# ts5_redraw.net
KiCad netlist of a schematic drawn in EAGLE
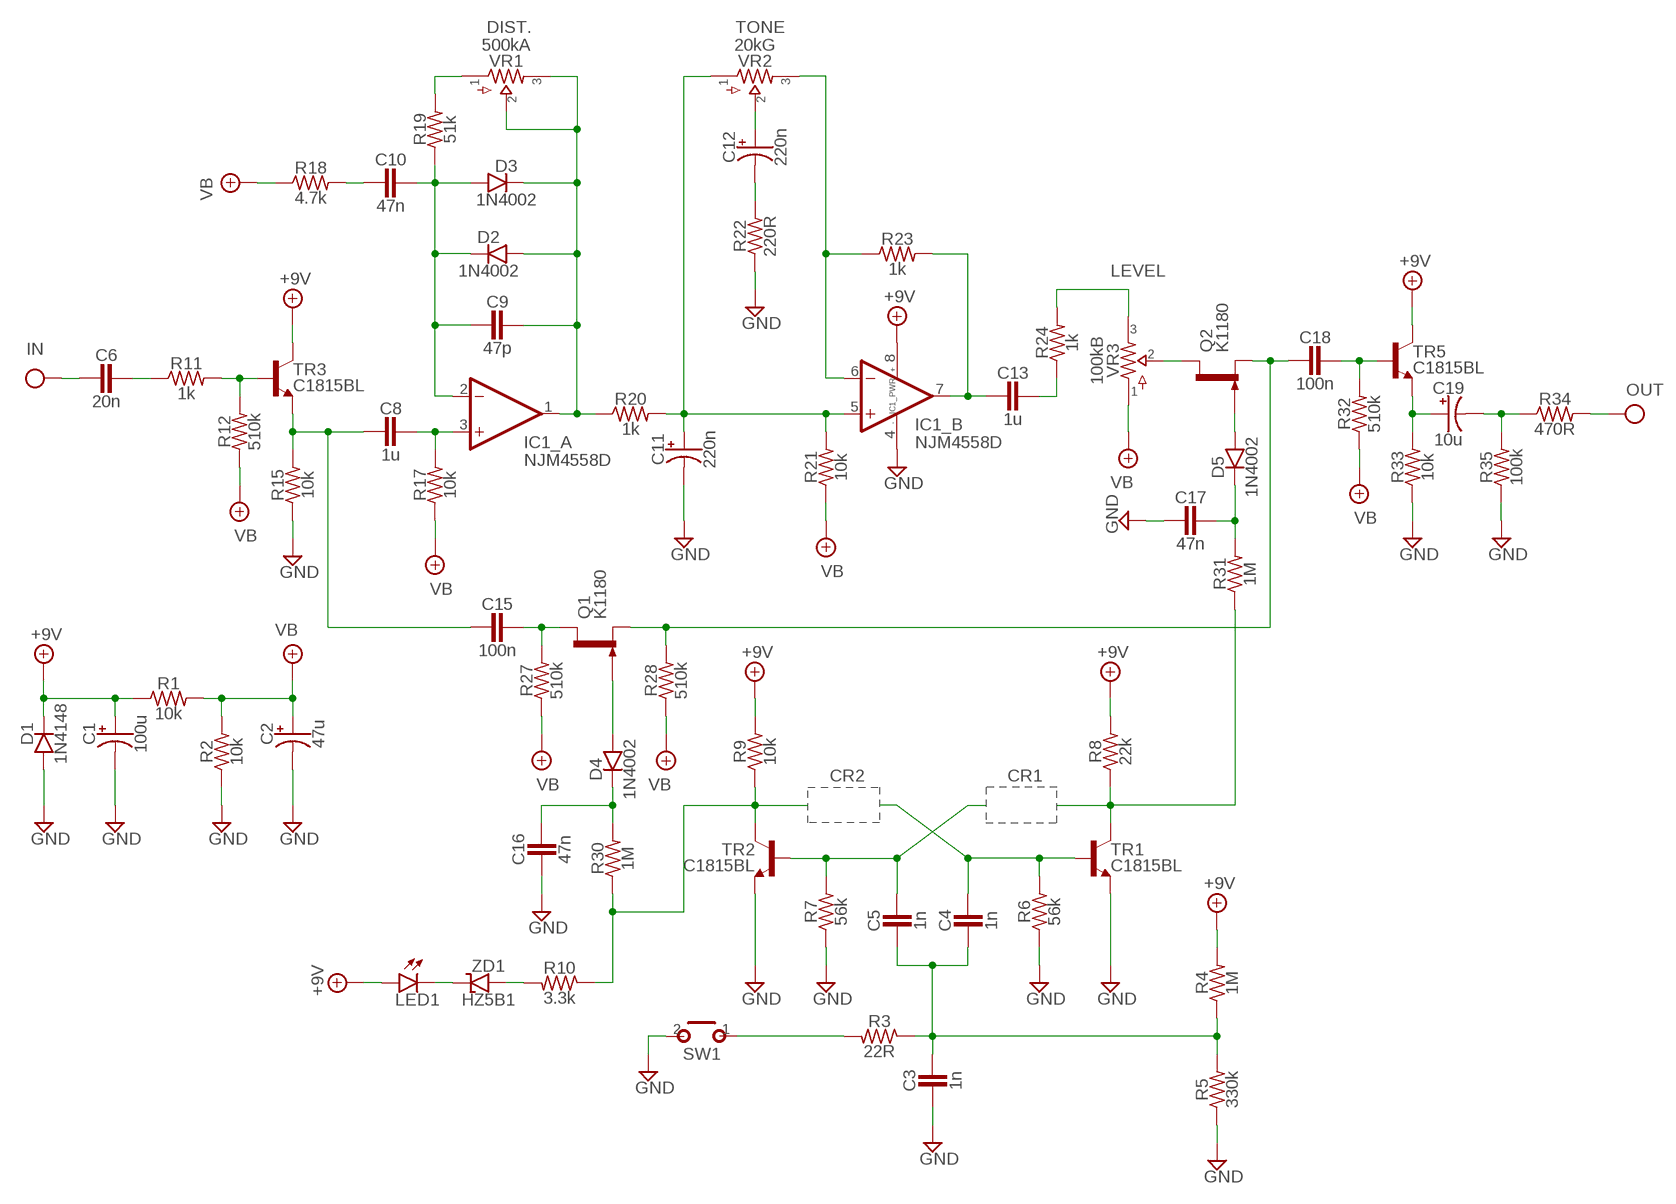
[diagram p0: schematic, sheet 1]

(export (version "E")
  (design (tool "Eeschema 10.0.6"))
  (components
    (comp (ref "C1")
      (value "100u")
      (footprint "eagle-import:050_020")
      (libsource (lib "eagle-import") (part "0500"))
    )
    (comp (ref "C2")
      (value "47u")
      (footprint "eagle-import:050_020")
      (libsource (lib "eagle-import") (part "0500"))
    )
    (comp (ref "C3")
      (value "1n")
      (footprint "eagle-import:BOX_SMALL")
      (libsource (lib "eagle-import") (part "CER/FILMBOX.1"))
    )
    (comp (ref "C4")
      (value "1n")
      (footprint "eagle-import:BOX_SMALL")
      (libsource (lib "eagle-import") (part "CER/FILMBOX.1"))
    )
    (comp (ref "C5")
      (value "1n")
      (footprint "eagle-import:BOX_SMALL")
      (libsource (lib "eagle-import") (part "CER/FILMBOX.1"))
    )
    (comp (ref "C6")
      (value "20n")
      (footprint "eagle-import:BOX_SMALL")
      (libsource (lib "eagle-import") (part "CER/FILMBOX.1"))
    )
    (comp (ref "C8")
      (value "1u")
      (footprint "eagle-import:BOX_SMALL")
      (libsource (lib "eagle-import") (part "CER/FILMBOX.1"))
    )
    (comp (ref "C9")
      (value "47p")
      (footprint "eagle-import:BOX_SMALL")
      (libsource (lib "eagle-import") (part "CER/FILMBOX.1"))
    )
    (comp (ref "C10")
      (value "47n")
      (footprint "eagle-import:BOX_SMALL")
      (libsource (lib "eagle-import") (part "CER/FILMBOX.1"))
    )
    (comp (ref "C11")
      (value "220n")
      (footprint "eagle-import:050_020")
      (libsource (lib "eagle-import") (part "0500"))
    )
    (comp (ref "C12")
      (value "220n")
      (footprint "eagle-import:050_020")
      (libsource (lib "eagle-import") (part "0500"))
    )
    (comp (ref "C13")
      (value "1u")
      (footprint "eagle-import:BOX_SMALL")
      (libsource (lib "eagle-import") (part "CER/FILMBOX.1"))
    )
    (comp (ref "C15")
      (value "100n")
      (footprint "eagle-import:BOX_SMALL")
      (libsource (lib "eagle-import") (part "CER/FILMBOX.1"))
    )
    (comp (ref "C16")
      (value "47n")
      (footprint "eagle-import:BOX_SMALL")
      (libsource (lib "eagle-import") (part "CER/FILMBOX.1"))
    )
    (comp (ref "C17")
      (value "47n")
      (footprint "eagle-import:BOX_SMALL")
      (libsource (lib "eagle-import") (part "CER/FILMBOX.1"))
    )
    (comp (ref "C18")
      (value "100n")
      (footprint "eagle-import:BOX_SMALL")
      (libsource (lib "eagle-import") (part "CER/FILMBOX.1"))
    )
    (comp (ref "C19")
      (value "10u")
      (footprint "eagle-import:050_020")
      (libsource (lib "eagle-import") (part "0500"))
    )
    (comp (ref "D1")
      (value "1N4148")
      (footprint "eagle-import:DO35-2")
      (libsource (lib "eagle-import") (part "DO35.2"))
    )
    (comp (ref "D2")
      (value "1N4002")
      (footprint "eagle-import:DO35-2")
      (libsource (lib "eagle-import") (part "DO35.2"))
    )
    (comp (ref "D3")
      (value "1N4002")
      (footprint "eagle-import:DO35-2")
      (libsource (lib "eagle-import") (part "DO35.2"))
    )
    (comp (ref "D4")
      (value "1N4002")
      (footprint "eagle-import:DO35-2")
      (libsource (lib "eagle-import") (part "DO35.2"))
    )
    (comp (ref "D5")
      (value "1N4002")
      (footprint "eagle-import:DO35-2")
      (libsource (lib "eagle-import") (part "DO35.2"))
    )
    (comp (ref "IC1")
      (value "NJM4558D")
      (footprint "eagle-import:DIL0")
      (libsource (lib "eagle-import") (part "DUALTH"))
    )
    (comp (ref "LED1")
      (value "TLR124")
      (footprint "eagle-import:3MM_D")
      (libsource (lib "eagle-import") (part "LED"))
    )
    (comp (ref "Q1")
      (value "K1180")
      (footprint "eagle-import:TO92-")
      (libsource (lib "eagle-import") (part "2N5457"))
    )
    (comp (ref "Q2")
      (value "K1180")
      (footprint "eagle-import:TO92-")
      (libsource (lib "eagle-import") (part "2N5457"))
    )
    (comp (ref "R1")
      (value "10k")
      (footprint "eagle-import:R0207_3")
      (libsource (lib "eagle-import") (part "R_.3B"))
    )
    (comp (ref "R2")
      (value "10k")
      (footprint "eagle-import:R0207_3")
      (libsource (lib "eagle-import") (part "R_.3B"))
    )
    (comp (ref "R3")
      (value "22R")
      (footprint "eagle-import:R0207_3")
      (libsource (lib "eagle-import") (part "R_.3B"))
    )
    (comp (ref "R4")
      (value "1M")
      (footprint "eagle-import:R0207_3")
      (libsource (lib "eagle-import") (part "R_.3B"))
    )
    (comp (ref "R5")
      (value "330k")
      (footprint "eagle-import:R0207_3")
      (libsource (lib "eagle-import") (part "R_.3B"))
    )
    (comp (ref "R6")
      (value "56k")
      (footprint "eagle-import:R0207_3")
      (libsource (lib "eagle-import") (part "R_.3B"))
    )
    (comp (ref "R7")
      (value "56k")
      (footprint "eagle-import:R0207_3")
      (libsource (lib "eagle-import") (part "R_.3B"))
    )
    (comp (ref "R8")
      (value "22k")
      (footprint "eagle-import:R0207_3")
      (libsource (lib "eagle-import") (part "R_.3B"))
    )
    (comp (ref "R9")
      (value "10k")
      (footprint "eagle-import:R0207_3")
      (libsource (lib "eagle-import") (part "R_.3B"))
    )
    (comp (ref "R10")
      (value "3.3k")
      (footprint "eagle-import:R0207_3")
      (libsource (lib "eagle-import") (part "R_.3B"))
    )
    (comp (ref "R11")
      (value "1k")
      (footprint "eagle-import:R0207_3")
      (libsource (lib "eagle-import") (part "R_.3B"))
    )
    (comp (ref "R12")
      (value "510k")
      (footprint "eagle-import:R0207_3")
      (libsource (lib "eagle-import") (part "R_.3B"))
    )
    (comp (ref "R15")
      (value "10k")
      (footprint "eagle-import:R0207_3")
      (libsource (lib "eagle-import") (part "R_.3B"))
    )
    (comp (ref "R17")
      (value "10k")
      (footprint "eagle-import:R0207_3")
      (libsource (lib "eagle-import") (part "R_.3B"))
    )
    (comp (ref "R18")
      (value "4.7k")
      (footprint "eagle-import:R0207_3")
      (libsource (lib "eagle-import") (part "R_.3B"))
    )
    (comp (ref "R19")
      (value "51k")
      (footprint "eagle-import:R0207_3")
      (libsource (lib "eagle-import") (part "R_.3B"))
    )
    (comp (ref "R20")
      (value "1k")
      (footprint "eagle-import:R0207_3")
      (libsource (lib "eagle-import") (part "R_.3B"))
    )
    (comp (ref "R21")
      (value "10k")
      (footprint "eagle-import:R0207_3")
      (libsource (lib "eagle-import") (part "R_.3B"))
    )
    (comp (ref "R22")
      (value "220R")
      (footprint "eagle-import:R0207_3")
      (libsource (lib "eagle-import") (part "R_.3B"))
    )
    (comp (ref "R23")
      (value "1k")
      (footprint "eagle-import:R0207_3")
      (libsource (lib "eagle-import") (part "R_.3B"))
    )
    (comp (ref "R24")
      (value "1k")
      (footprint "eagle-import:R0207_3")
      (libsource (lib "eagle-import") (part "R_.3B"))
    )
    (comp (ref "R27")
      (value "510k")
      (footprint "eagle-import:R0207_3")
      (libsource (lib "eagle-import") (part "R_.3B"))
    )
    (comp (ref "R28")
      (value "510k")
      (footprint "eagle-import:R0207_3")
      (libsource (lib "eagle-import") (part "R_.3B"))
    )
    (comp (ref "R30")
      (value "1M")
      (footprint "eagle-import:R0207_3")
      (libsource (lib "eagle-import") (part "R_.3B"))
    )
    (comp (ref "R31")
      (value "1M")
      (footprint "eagle-import:R0207_3")
      (libsource (lib "eagle-import") (part "R_.3B"))
    )
    (comp (ref "R32")
      (value "510k")
      (footprint "eagle-import:R0207_3")
      (libsource (lib "eagle-import") (part "R_.3B"))
    )
    (comp (ref "R33")
      (value "10k")
      (footprint "eagle-import:R0207_3")
      (libsource (lib "eagle-import") (part "R_.3B"))
    )
    (comp (ref "R34")
      (value "470R")
      (footprint "eagle-import:R0207_3")
      (libsource (lib "eagle-import") (part "R_.3B"))
    )
    (comp (ref "R35")
      (value "100k")
      (footprint "eagle-import:R0207_3")
      (libsource (lib "eagle-import") (part "R_.3B"))
    )
    (comp (ref "SW1")
      (value "MOMENTARY")
      (footprint "eagle-import:SPST")
      (libsource (lib "eagle-import") (part "MOMENTARY"))
    )
    (comp (ref "TR1")
      (value "C1815BL")
      (footprint "eagle-import:TO92-")
      (libsource (lib "eagle-import") (part "2SC828A"))
    )
    (comp (ref "TR2")
      (value "C1815BL")
      (footprint "eagle-import:TO92-")
      (libsource (lib "eagle-import") (part "2SC828A"))
    )
    (comp (ref "TR3")
      (value "C1815BL")
      (footprint "eagle-import:TO92-")
      (libsource (lib "eagle-import") (part "2N3904"))
    )
    (comp (ref "TR5")
      (value "C1815BL")
      (footprint "eagle-import:TO92-")
      (libsource (lib "eagle-import") (part "2N3904"))
    )
    (comp (ref "VR1")
      (value "500kA")
      (footprint "eagle-import:16MM")
      (libsource (lib "eagle-import") (part "POTS16MM"))
    )
    (comp (ref "VR2")
      (value "20kG")
      (footprint "eagle-import:16MM")
      (libsource (lib "eagle-import") (part "POTS16MM"))
    )
    (comp (ref "VR3")
      (value "100kB")
      (footprint "eagle-import:16MM")
      (libsource (lib "eagle-import") (part "POTS16MM"))
    )
    (comp (ref "ZD1")
      (value "HZ5B1")
      (footprint "eagle-import:DO41-2")
      (libsource (lib "eagle-import") (part "ZENER.2"))
    )
  )
  (nets
    (net (code "1") (name "+9V") (class "Default")
      (node (ref "C1") (pin "+") (pinfunction "+_+") (pintype "passive"))
      (node (ref "D1") (pin "C") (pinfunction "C_C") (pintype "passive"))
      (node (ref "IC1") (pin "8") (pinfunction "V+_8") (pintype "power_in"))
      (node (ref "LED1") (pin "ANODE") (pinfunction "A_ANODE") (pintype "passive"))
      (node (ref "R1") (pin "1") (pinfunction "1_1") (pintype "passive"))
      (node (ref "R4") (pin "2") (pinfunction "2_2") (pintype "passive"))
      (node (ref "R8") (pin "2") (pinfunction "2_2") (pintype "passive"))
      (node (ref "R9") (pin "2") (pinfunction "2_2") (pintype "passive"))
      (node (ref "TR3") (pin "1") (pinfunction "C_1") (pintype "passive"))
      (node (ref "TR5") (pin "1") (pinfunction "C_1") (pintype "passive"))
    )
    (net (code "2") (name "GND") (class "Default")
      (node (ref "C1") (pin "-") (pinfunction "-_-") (pintype "passive"))
      (node (ref "C11") (pin "-") (pinfunction "-_-") (pintype "passive"))
      (node (ref "C16") (pin "2") (pinfunction "2_2") (pintype "passive"))
      (node (ref "C17") (pin "2") (pinfunction "2_2") (pintype "passive"))
      (node (ref "C2") (pin "-") (pinfunction "-_-") (pintype "passive"))
      (node (ref "C3") (pin "2") (pinfunction "2_2") (pintype "passive"))
      (node (ref "D1") (pin "A") (pinfunction "A_A") (pintype "passive"))
      (node (ref "IC1") (pin "4") (pinfunction "V-_4") (pintype "power_in"))
      (node (ref "R15") (pin "1") (pinfunction "1_1") (pintype "passive"))
      (node (ref "R2") (pin "1") (pinfunction "1_1") (pintype "passive"))
      (node (ref "R22") (pin "1") (pinfunction "1_1") (pintype "passive"))
      (node (ref "R33") (pin "1") (pinfunction "1_1") (pintype "passive"))
      (node (ref "R35") (pin "1") (pinfunction "1_1") (pintype "passive"))
      (node (ref "R5") (pin "1") (pinfunction "1_1") (pintype "passive"))
      (node (ref "R6") (pin "1") (pinfunction "1_1") (pintype "passive"))
      (node (ref "R7") (pin "1") (pinfunction "1_1") (pintype "passive"))
      (node (ref "SW1") (pin "2") (pinfunction "S_2") (pintype "passive"))
      (node (ref "TR1") (pin "3") (pinfunction "E_3") (pintype "passive"))
      (node (ref "TR2") (pin "3") (pinfunction "E_3") (pintype "passive"))
    )
    (net (code "3") (name "IN") (class "Default")
      (node (ref "C6") (pin "2") (pinfunction "2_2") (pintype "passive"))
    )
    (net (code "4") (name "Net-(C3-Pad1)") (class "Default")
      (node (ref "C3") (pin "1") (pinfunction "1_1") (pintype "passive"))
      (node (ref "C4") (pin "2") (pinfunction "2_2") (pintype "passive"))
      (node (ref "C5") (pin "2") (pinfunction "2_2") (pintype "passive"))
      (node (ref "R3") (pin "1") (pinfunction "1_1") (pintype "passive"))
      (node (ref "R4") (pin "1") (pinfunction "1_1") (pintype "passive"))
      (node (ref "R5") (pin "2") (pinfunction "2_2") (pintype "passive"))
    )
    (net (code "5") (name "Net-(C6-Pad1)") (class "Default")
      (node (ref "C6") (pin "1") (pinfunction "1_1") (pintype "passive"))
      (node (ref "R11") (pin "1") (pinfunction "1_1") (pintype "passive"))
    )
    (net (code "6") (name "Net-(C10-Pad2)") (class "Default")
      (node (ref "C10") (pin "2") (pinfunction "2_2") (pintype "passive"))
      (node (ref "R18") (pin "2") (pinfunction "2_2") (pintype "passive"))
    )
    (net (code "7") (name "Net-(C12-Pad+)") (class "Default")
      (node (ref "C12") (pin "+") (pinfunction "+_+") (pintype "passive"))
      (node (ref "VR2") (pin "2") (pinfunction "2_2") (pintype "passive"))
    )
    (net (code "8") (name "Net-(C12-Pad-)") (class "Default")
      (node (ref "C12") (pin "-") (pinfunction "-_-") (pintype "passive"))
      (node (ref "R22") (pin "2") (pinfunction "2_2") (pintype "passive"))
    )
    (net (code "9") (name "Net-(C13-Pad1)") (class "Default")
      (node (ref "C13") (pin "1") (pinfunction "1_1") (pintype "passive"))
      (node (ref "R24") (pin "1") (pinfunction "1_1") (pintype "passive"))
    )
    (net (code "10") (name "Net-(C16-Pad1)") (class "Default")
      (node (ref "C16") (pin "1") (pinfunction "1_1") (pintype "passive"))
      (node (ref "D4") (pin "C") (pinfunction "C_C") (pintype "passive"))
      (node (ref "R30") (pin "2") (pinfunction "2_2") (pintype "passive"))
    )
    (net (code "11") (name "Net-(C17-Pad1)") (class "Default")
      (node (ref "C17") (pin "1") (pinfunction "1_1") (pintype "passive"))
      (node (ref "D5") (pin "C") (pinfunction "C_C") (pintype "passive"))
      (node (ref "R31") (pin "2") (pinfunction "2_2") (pintype "passive"))
    )
    (net (code "12") (name "Net-(C19-Pad-)") (class "Default")
      (node (ref "C19") (pin "-") (pinfunction "-_-") (pintype "passive"))
      (node (ref "R34") (pin "1") (pinfunction "1_1") (pintype "passive"))
      (node (ref "R35") (pin "2") (pinfunction "2_2") (pintype "passive"))
    )
    (net (code "13") (name "Net-(IC1A-+IN)") (class "Default")
      (node (ref "C8") (pin "1") (pinfunction "1_1") (pintype "passive"))
      (node (ref "IC1") (pin "3") (pinfunction "+IN_3") (pintype "input"))
      (node (ref "R17") (pin "2") (pinfunction "2_2") (pintype "passive"))
    )
    (net (code "14") (name "Net-(IC1A--IN)") (class "Default")
      (node (ref "C10") (pin "1") (pinfunction "1_1") (pintype "passive"))
      (node (ref "C9") (pin "2") (pinfunction "2_2") (pintype "passive"))
      (node (ref "D2") (pin "C") (pinfunction "C_C") (pintype "passive"))
      (node (ref "D3") (pin "A") (pinfunction "A_A") (pintype "passive"))
      (node (ref "IC1") (pin "2") (pinfunction "-IN_2") (pintype "input"))
      (node (ref "R19") (pin "1") (pinfunction "1_1") (pintype "passive"))
    )
    (net (code "15") (name "Net-(IC1A-OUT)") (class "Default")
      (node (ref "C9") (pin "1") (pinfunction "1_1") (pintype "passive"))
      (node (ref "D2") (pin "A") (pinfunction "A_A") (pintype "passive"))
      (node (ref "D3") (pin "C") (pinfunction "C_C") (pintype "passive"))
      (node (ref "IC1") (pin "1") (pinfunction "OUT_1") (pintype "output"))
      (node (ref "R20") (pin "1") (pinfunction "1_1") (pintype "passive"))
      (node (ref "VR1") (pin "2") (pinfunction "2_2") (pintype "passive"))
      (node (ref "VR1") (pin "3") (pinfunction "3_3") (pintype "passive"))
    )
    (net (code "16") (name "Net-(IC1B-+IN)") (class "Default")
      (node (ref "C11") (pin "+") (pinfunction "+_+") (pintype "passive"))
      (node (ref "IC1") (pin "5") (pinfunction "+IN_5") (pintype "input"))
      (node (ref "R20") (pin "2") (pinfunction "2_2") (pintype "passive"))
      (node (ref "R21") (pin "2") (pinfunction "2_2") (pintype "passive"))
      (node (ref "VR2") (pin "1") (pinfunction "1_1") (pintype "passive"))
    )
    (net (code "17") (name "Net-(IC1B--IN)") (class "Default")
      (node (ref "IC1") (pin "6") (pinfunction "-IN_6") (pintype "input"))
      (node (ref "R23") (pin "1") (pinfunction "1_1") (pintype "passive"))
      (node (ref "VR2") (pin "3") (pinfunction "3_3") (pintype "passive"))
    )
    (net (code "18") (name "Net-(IC1B-OUT)") (class "Default")
      (node (ref "C13") (pin "2") (pinfunction "2_2") (pintype "passive"))
      (node (ref "IC1") (pin "7") (pinfunction "OUT_7") (pintype "output"))
      (node (ref "R23") (pin "2") (pinfunction "2_2") (pintype "passive"))
    )
    (net (code "19") (name "Net-(LED1-C)") (class "Default")
      (node (ref "LED1") (pin "P$1") (pinfunction "C_P$1") (pintype "passive"))
      (node (ref "ZD1") (pin "C") (pinfunction "C_C") (pintype "passive"))
    )
    (net (code "20") (name "Net-(Q1-D)") (class "Default")
      (node (ref "C15") (pin "1") (pinfunction "1_1") (pintype "passive"))
      (node (ref "Q1") (pin "3") (pinfunction "D_3") (pintype "passive"))
      (node (ref "R27") (pin "2") (pinfunction "2_2") (pintype "passive"))
    )
    (net (code "21") (name "Net-(Q1-G)") (class "Default")
      (node (ref "D4") (pin "A") (pinfunction "A_A") (pintype "passive"))
      (node (ref "Q1") (pin "1") (pinfunction "G_1") (pintype "passive"))
    )
    (net (code "22") (name "Net-(Q1-S)") (class "Default")
      (node (ref "C18") (pin "2") (pinfunction "2_2") (pintype "passive"))
      (node (ref "Q1") (pin "2") (pinfunction "S_2") (pintype "passive"))
      (node (ref "Q2") (pin "2") (pinfunction "S_2") (pintype "passive"))
      (node (ref "R28") (pin "2") (pinfunction "2_2") (pintype "passive"))
    )
    (net (code "23") (name "Net-(Q2-D)") (class "Default")
      (node (ref "Q2") (pin "3") (pinfunction "D_3") (pintype "passive"))
      (node (ref "VR3") (pin "2") (pinfunction "2_2") (pintype "passive"))
    )
    (net (code "24") (name "Net-(Q2-G)") (class "Default")
      (node (ref "D5") (pin "A") (pinfunction "A_A") (pintype "passive"))
      (node (ref "Q2") (pin "1") (pinfunction "G_1") (pintype "passive"))
    )
    (net (code "25") (name "Net-(R10-Pad2)") (class "Default")
      (node (ref "R10") (pin "2") (pinfunction "2_2") (pintype "passive"))
      (node (ref "ZD1") (pin "A") (pinfunction "A_A") (pintype "passive"))
    )
    (net (code "26") (name "Net-(R19-Pad2)") (class "Default")
      (node (ref "R19") (pin "2") (pinfunction "2_2") (pintype "passive"))
      (node (ref "VR1") (pin "1") (pinfunction "1_1") (pintype "passive"))
    )
    (net (code "27") (name "Net-(R24-Pad2)") (class "Default")
      (node (ref "R24") (pin "2") (pinfunction "2_2") (pintype "passive"))
      (node (ref "VR3") (pin "3") (pinfunction "3_3") (pintype "passive"))
    )
    (net (code "28") (name "Net-(SW1-P)") (class "Default")
      (node (ref "R3") (pin "2") (pinfunction "2_2") (pintype "passive"))
      (node (ref "SW1") (pin "1") (pinfunction "P_1") (pintype "passive"))
    )
    (net (code "29") (name "Net-(TR1-B)") (class "Default")
      (node (ref "C4") (pin "1") (pinfunction "1_1") (pintype "passive"))
      (node (ref "R6") (pin "2") (pinfunction "2_2") (pintype "passive"))
      (node (ref "TR1") (pin "1") (pinfunction "B_1") (pintype "passive"))
    )
    (net (code "30") (name "Net-(TR1-C)") (class "Default")
      (node (ref "R31") (pin "1") (pinfunction "1_1") (pintype "passive"))
      (node (ref "R8") (pin "1") (pinfunction "1_1") (pintype "passive"))
      (node (ref "TR1") (pin "2") (pinfunction "C_2") (pintype "passive"))
    )
    (net (code "31") (name "Net-(TR2-B)") (class "Default")
      (node (ref "C5") (pin "1") (pinfunction "1_1") (pintype "passive"))
      (node (ref "R7") (pin "2") (pinfunction "2_2") (pintype "passive"))
      (node (ref "TR2") (pin "1") (pinfunction "B_1") (pintype "passive"))
    )
    (net (code "32") (name "Net-(TR2-C)") (class "Default")
      (node (ref "R10") (pin "1") (pinfunction "1_1") (pintype "passive"))
      (node (ref "R30") (pin "1") (pinfunction "1_1") (pintype "passive"))
      (node (ref "R9") (pin "1") (pinfunction "1_1") (pintype "passive"))
      (node (ref "TR2") (pin "2") (pinfunction "C_2") (pintype "passive"))
    )
    (net (code "33") (name "Net-(TR3-B)") (class "Default")
      (node (ref "R11") (pin "2") (pinfunction "2_2") (pintype "passive"))
      (node (ref "R12") (pin "2") (pinfunction "2_2") (pintype "passive"))
      (node (ref "TR3") (pin "2") (pinfunction "B_2") (pintype "passive"))
    )
    (net (code "34") (name "Net-(TR3-E)") (class "Default")
      (node (ref "C15") (pin "2") (pinfunction "2_2") (pintype "passive"))
      (node (ref "C8") (pin "2") (pinfunction "2_2") (pintype "passive"))
      (node (ref "R15") (pin "2") (pinfunction "2_2") (pintype "passive"))
      (node (ref "TR3") (pin "3") (pinfunction "E_3") (pintype "passive"))
    )
    (net (code "35") (name "Net-(TR5-B)") (class "Default")
      (node (ref "C18") (pin "1") (pinfunction "1_1") (pintype "passive"))
      (node (ref "R32") (pin "2") (pinfunction "2_2") (pintype "passive"))
      (node (ref "TR5") (pin "2") (pinfunction "B_2") (pintype "passive"))
    )
    (net (code "36") (name "Net-(TR5-E)") (class "Default")
      (node (ref "C19") (pin "+") (pinfunction "+_+") (pintype "passive"))
      (node (ref "R33") (pin "2") (pinfunction "2_2") (pintype "passive"))
      (node (ref "TR5") (pin "3") (pinfunction "E_3") (pintype "passive"))
    )
    (net (code "37") (name "OUT") (class "Default")
      (node (ref "R34") (pin "2") (pinfunction "2_2") (pintype "passive"))
    )
    (net (code "38") (name "VB") (class "Default")
      (node (ref "C2") (pin "+") (pinfunction "+_+") (pintype "passive"))
      (node (ref "R1") (pin "2") (pinfunction "2_2") (pintype "passive"))
      (node (ref "R12") (pin "1") (pinfunction "1_1") (pintype "passive"))
      (node (ref "R17") (pin "1") (pinfunction "1_1") (pintype "passive"))
      (node (ref "R18") (pin "1") (pinfunction "1_1") (pintype "passive"))
      (node (ref "R2") (pin "2") (pinfunction "2_2") (pintype "passive"))
      (node (ref "R21") (pin "1") (pinfunction "1_1") (pintype "passive"))
      (node (ref "R27") (pin "1") (pinfunction "1_1") (pintype "passive"))
      (node (ref "R28") (pin "1") (pinfunction "1_1") (pintype "passive"))
      (node (ref "R32") (pin "1") (pinfunction "1_1") (pintype "passive"))
      (node (ref "VR3") (pin "1") (pinfunction "1_1") (pintype "passive"))
    )
  )
)
